# cell.net
KiCad netlist of a schematic drawn in EAGLE
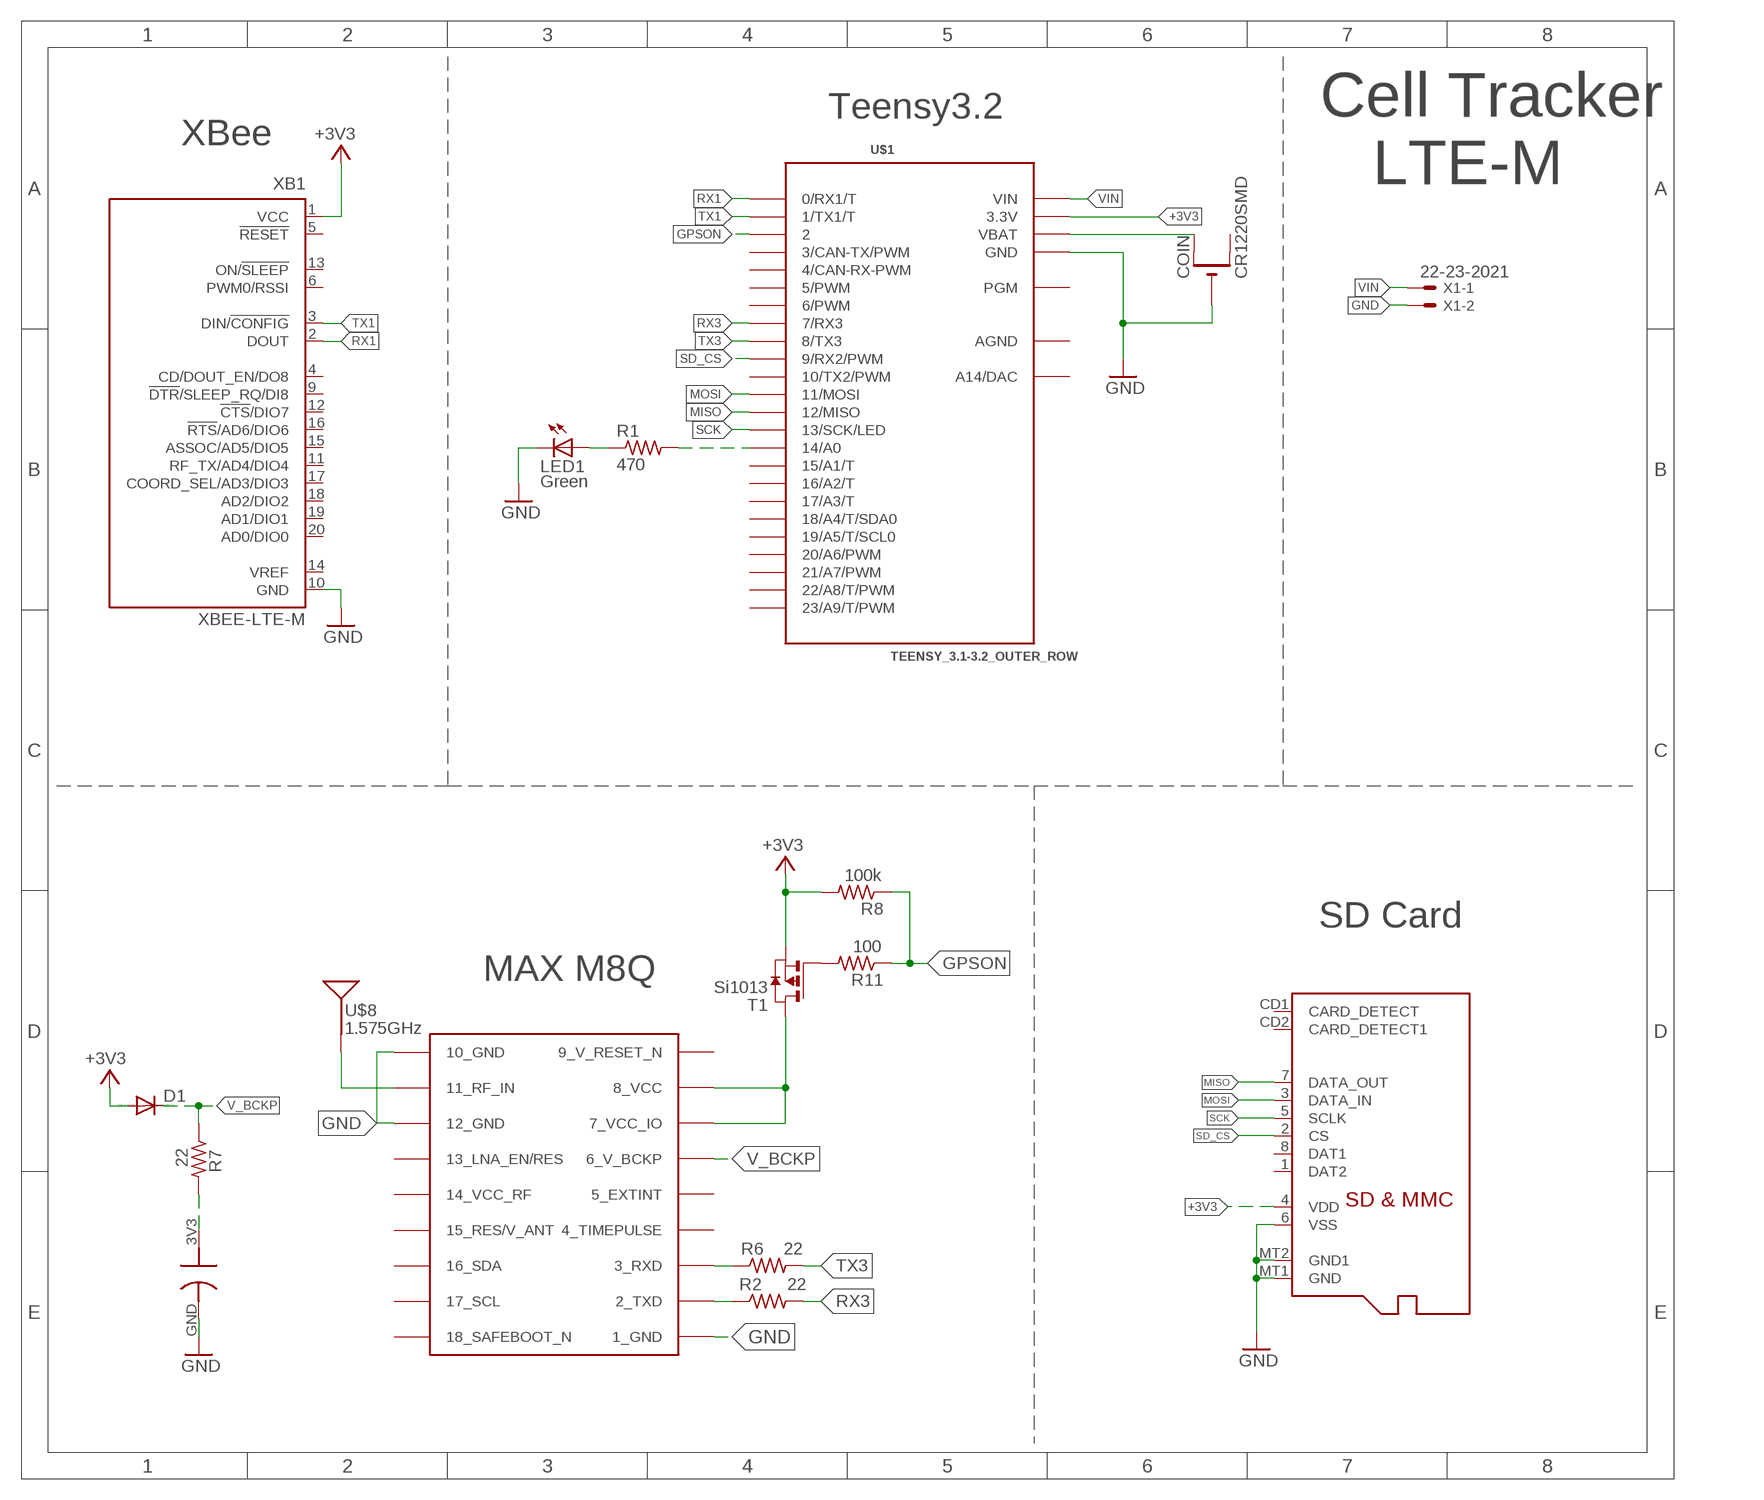
[diagram p0: schematic, sheet 1]

(export (version "E")
  (design (tool "Eeschema 10.0.6"))
  (components
    (comp (ref "C1")
      (value "DCK-3R3E204T614-E")
      (footprint "eagle-import:ELNASUPERCAP")
      (libsource (lib "eagle-import") (part "DCK-3R3E204T614-E"))
    )
    (comp (ref "COIN")
      (value "CR1220SMD")
      (footprint "eagle-import:CR1220-SMD")
      (libsource (lib "eagle-import") (part "CR1220SMT"))
    )
    (comp (ref "D1")
      (value "DIODE-SOD523")
      (footprint "eagle-import:SOD523")
      (libsource (lib "eagle-import") (part "DIODE-SOD523"))
    )
    (comp (ref "LED1")
      (value "Green")
      (footprint "eagle-import:CHIP-LED0603")
      (libsource (lib "eagle-import") (part "LEDCHIP-LED0603"))
    )
    (comp (ref "R1")
      (value "470")
      (footprint "eagle-import:R0603")
      (libsource (lib "eagle-import") (part "resistor_348_R-US_R0603"))
    )
    (comp (ref "R2")
      (value "22")
      (footprint "eagle-import:R0603")
      (libsource (lib "eagle-import") (part "R-US_R0603"))
    )
    (comp (ref "R6")
      (value "22")
      (footprint "eagle-import:R0603")
      (libsource (lib "eagle-import") (part "R-US_R0603"))
    )
    (comp (ref "R7")
      (value "22")
      (footprint "eagle-import:R0603")
      (libsource (lib "eagle-import") (part "R-US_R0603"))
    )
    (comp (ref "R8")
      (value "100k")
      (footprint "eagle-import:R0603")
      (libsource (lib "eagle-import") (part "R-US_R0603"))
    )
    (comp (ref "R11")
      (value "100")
      (footprint "eagle-import:R0603")
      (libsource (lib "eagle-import") (part "R-US_R0603"))
    )
    (comp (ref "T1")
      (value "Si1013")
      (footprint "eagle-import:SOT-23")
      (libsource (lib "eagle-import") (part "PMOSSOT23"))
    )
    (comp (ref "U$1")
      (value "TEENSY_3.1-3.2_OUTER_ROW")
      (footprint "eagle-import:TEENSY_3.0-3.2&LC_OUTER_ROW")
      (libsource (lib "eagle-import") (part "TEENSY_3.1-3.2_OUTER_ROW"))
    )
    (comp (ref "U$2")
      (value "MICROSD")
      (footprint "eagle-import:MICROSD")
      (libsource (lib "eagle-import") (part "MICROSD"))
    )
    (comp (ref "U$7")
      (value "MAX-M8")
      (footprint "eagle-import:MAX-M8")
      (libsource (lib "eagle-import") (part "MAX-M8"))
    )
    (comp (ref "U$8")
      (value "1.575GHz")
      (footprint "eagle-import:SPARKFUN-GPS_ANT-GPS-2X7MM")
      (libsource (lib "eagle-import") (part "SPARKFUN-GPS_ANTENNAGPS-2X7MM"))
    )
    (comp (ref "X1")
      (value "22-23-2021")
      (footprint "eagle-import:22-23-2021")
      (fields (field (name "MF") "MOLEX"))
      (libsource (lib "eagle-import") (part "22-23-2021"))
    )
    (comp (ref "XB1")
      (value "XBEE-LTE-M")
      (footprint "eagle-import:XBEE-PRO")
      (fields (field (name "MPN") "XBP24-AWI-001"))
      (libsource (lib "eagle-import") (part "XBEE-PRO"))
    )
  )
  (nets
    (net (code "1") (name "+3V3") (class "Default")
      (node (ref "D1") (pin "A") (pinfunction "A_A") (pintype "passive"))
      (node (ref "R8") (pin "2") (pinfunction "2_2") (pintype "passive"))
      (node (ref "T1") (pin "2") (pinfunction "S_2") (pintype "passive"))
      (node (ref "U$1") (pin "3.3V") (pinfunction "3.3V_3.3V") (pintype "power_in"))
      (node (ref "U$1") (pin "3.3V1") (pinfunction "3.3V_3.3V1") (pintype "power_in"))
      (node (ref "U$2") (pin "4") (pinfunction "VDD_4") (pintype "power_in"))
      (node (ref "XB1") (pin "1") (pinfunction "VCC_1") (pintype "power_in"))
    )
    (net (code "2") (name "/9_V_RESET_N") (class "Default")
      (node (ref "U$7") (pin "9_RESET_N") (pinfunction "9_V_RESET_N_9_RESET_N") (pintype "power_in"))
    )
    (net (code "3") (name "/AGND") (class "Default")
      (node (ref "U$1") (pin "AGND") (pinfunction "AGND_AGND") (pintype "power_in"))
    )
    (net (code "4") (name "GND") (class "Default")
      (node (ref "C1") (pin "GND") (pinfunction "GND_GND") (pintype "bidirectional"))
      (node (ref "COIN") (pin "-") (pinfunction "-_-") (pintype "passive"))
      (node (ref "LED1") (pin "C") (pinfunction "C_C") (pintype "passive"))
      (node (ref "U$1") (pin "GND") (pinfunction "GND_GND") (pintype "power_in"))
      (node (ref "U$1") (pin "GND1") (pinfunction "GND_GND1") (pintype "power_in"))
      (node (ref "U$2") (pin "6") (pinfunction "VSS_6") (pintype "power_in"))
      (node (ref "U$2") (pin "MT1") (pinfunction "GND_MT1") (pintype "power_in"))
      (node (ref "U$2") (pin "MT2") (pinfunction "GND1_MT2") (pintype "power_in"))
      (node (ref "U$7") (pin "10_GND") (pinfunction "10_GND_10_GND") (pintype "power_in"))
      (node (ref "U$7") (pin "12_GND") (pinfunction "12_GND_12_GND") (pintype "power_in"))
      (node (ref "U$7") (pin "1_GND") (pinfunction "1_GND_1_GND") (pintype "power_in"))
      (node (ref "X1") (pin "2") (pinfunction "S_2") (pintype "passive"))
      (node (ref "XB1") (pin "10") (pinfunction "GND_10") (pintype "power_in"))
    )
    (net (code "5") (name "GPSON") (class "Default")
      (node (ref "R11") (pin "1") (pinfunction "1_1") (pintype "passive"))
      (node (ref "R8") (pin "1") (pinfunction "1_1") (pintype "passive"))
      (node (ref "U$1") (pin "2") (pinfunction "2_2") (pintype "bidirectional"))
    )
    (net (code "6") (name "MISO") (class "Default")
      (node (ref "U$1") (pin "12") (pinfunction "12/MISO_12") (pintype "bidirectional"))
      (node (ref "U$2") (pin "7") (pinfunction "DATA_OUT_7") (pintype "output"))
    )
    (net (code "7") (name "MOSI") (class "Default")
      (node (ref "U$1") (pin "11") (pinfunction "11/MOSI_11") (pintype "bidirectional"))
      (node (ref "U$2") (pin "3") (pinfunction "DATA_IN_3") (pintype "input"))
    )
    (net (code "8") (name "Net-(C1-Pad3V3)") (class "Default")
      (node (ref "C1") (pin "3V3") (pinfunction "3V3_3V3") (pintype "bidirectional"))
      (node (ref "R7") (pin "2") (pinfunction "2_2") (pintype "passive"))
    )
    (net (code "9") (name "Net-(COIN-+)") (class "Default")
      (node (ref "COIN") (pin "+$1") (pinfunction "+_+$1") (pintype "passive"))
      (node (ref "U$1") (pin "VBAT") (pinfunction "VBAT_VBAT") (pintype "power_in"))
    )
    (net (code "10") (name "Net-(LED1-PadA)") (class "Default")
      (node (ref "LED1") (pin "A") (pinfunction "A_A") (pintype "passive"))
      (node (ref "R1") (pin "1") (pinfunction "1_1") (pintype "passive"))
    )
    (net (code "11") (name "Net-(R1-Pad2)") (class "Default")
      (node (ref "R1") (pin "2") (pinfunction "2_2") (pintype "passive"))
      (node (ref "U$1") (pin "14/A0") (pinfunction "14/A0_14/A0") (pintype "bidirectional"))
    )
    (net (code "12") (name "Net-(R2-Pad1)") (class "Default")
      (node (ref "R2") (pin "1") (pinfunction "1_1") (pintype "passive"))
      (node (ref "U$7") (pin "2_TXD") (pinfunction "2_TXD_2_TXD") (pintype "bidirectional"))
    )
    (net (code "13") (name "Net-(R6-Pad1)") (class "Default")
      (node (ref "R6") (pin "1") (pinfunction "1_1") (pintype "passive"))
      (node (ref "U$7") (pin "3_RXD") (pinfunction "3_RXD_3_RXD") (pintype "bidirectional"))
    )
    (net (code "14") (name "Net-(T1-D)") (class "Default")
      (node (ref "T1") (pin "1") (pinfunction "D_1") (pintype "passive"))
      (node (ref "U$7") (pin "7_VCC_IO") (pinfunction "7_VCC_IO_7_VCC_IO") (pintype "power_in"))
      (node (ref "U$7") (pin "8_VCC") (pinfunction "8_VCC_8_VCC") (pintype "power_in"))
    )
    (net (code "15") (name "Net-(T1-G)") (class "Default")
      (node (ref "R11") (pin "2") (pinfunction "2_2") (pintype "passive"))
      (node (ref "T1") (pin "3") (pinfunction "G_3") (pintype "passive"))
    )
    (net (code "16") (name "Net-(U$8-SIGNAL)") (class "Default")
      (node (ref "U$7") (pin "11_RF_IN") (pinfunction "11_RF_IN_11_RF_IN") (pintype "bidirectional"))
      (node (ref "U$8") (pin "1") (pinfunction "SIGNAL_1") (pintype "bidirectional"))
    )
    (net (code "17") (name "RX1") (class "Default")
      (node (ref "U$1") (pin "0") (pinfunction "0/RX1/T_0") (pintype "bidirectional"))
      (node (ref "XB1") (pin "2") (pinfunction "DOUT_2") (pintype "output"))
    )
    (net (code "18") (name "RX3") (class "Default")
      (node (ref "R2") (pin "2") (pinfunction "2_2") (pintype "passive"))
      (node (ref "U$1") (pin "7") (pinfunction "7/RX3_7") (pintype "bidirectional"))
    )
    (net (code "19") (name "SCK") (class "Default")
      (node (ref "U$1") (pin "13") (pinfunction "13/SCK/LED_13") (pintype "bidirectional"))
      (node (ref "U$2") (pin "5") (pinfunction "SCLK_5") (pintype "input"))
    )
    (net (code "20") (name "SD_CS") (class "Default")
      (node (ref "U$1") (pin "9") (pinfunction "9/RX2/PWM_9") (pintype "bidirectional"))
      (node (ref "U$2") (pin "2") (pinfunction "CS_2") (pintype "input"))
    )
    (net (code "21") (name "TX1") (class "Default")
      (node (ref "U$1") (pin "1") (pinfunction "1/TX1/T_1") (pintype "bidirectional"))
      (node (ref "XB1") (pin "3") (pinfunction "DIN/~{CONFIG}_3") (pintype "input"))
    )
    (net (code "22") (name "TX3") (class "Default")
      (node (ref "R6") (pin "2") (pinfunction "2_2") (pintype "passive"))
      (node (ref "U$1") (pin "8") (pinfunction "8/TX3_8") (pintype "bidirectional"))
    )
    (net (code "23") (name "VIN") (class "Default")
      (node (ref "U$1") (pin "VIN") (pinfunction "VIN_VIN") (pintype "power_in"))
      (node (ref "X1") (pin "1") (pinfunction "S_1") (pintype "passive"))
    )
    (net (code "24") (name "V_BCKP") (class "Default")
      (node (ref "D1") (pin "C") (pinfunction "C_C") (pintype "passive"))
      (node (ref "R7") (pin "1") (pinfunction "1_1") (pintype "passive"))
      (node (ref "U$7") (pin "6_V_BCKP") (pinfunction "6_V_BCKP_6_V_BCKP") (pintype "bidirectional"))
    )
    (net (code "25") (name "unconnected-(COIN-+1-Pad+$2)") (class "Default")
      (node (ref "COIN") (pin "+$2") (pinfunction "+1_+$2") (pintype "passive"))
    )
    (net (code "26") (name "unconnected-(U$1-3{slash}CAN-TX{slash}PWM-Pad3)") (class "Default")
      (node (ref "U$1") (pin "3") (pinfunction "3/CAN-TX/PWM_3") (pintype "bidirectional"))
    )
    (net (code "27") (name "unconnected-(U$1-4{slash}CAN-RX-PWM-Pad4)") (class "Default")
      (node (ref "U$1") (pin "4") (pinfunction "4/CAN-RX-PWM_4") (pintype "bidirectional"))
    )
    (net (code "28") (name "unconnected-(U$1-5{slash}PWM-Pad5)") (class "Default")
      (node (ref "U$1") (pin "5") (pinfunction "5/PWM_5") (pintype "bidirectional"))
    )
    (net (code "29") (name "unconnected-(U$1-6{slash}PWM-Pad6)") (class "Default")
      (node (ref "U$1") (pin "6") (pinfunction "6/PWM_6") (pintype "bidirectional"))
    )
    (net (code "30") (name "unconnected-(U$1-10{slash}TX2{slash}PWM-Pad10)") (class "Default")
      (node (ref "U$1") (pin "10") (pinfunction "10/TX2/PWM_10") (pintype "bidirectional"))
    )
    (net (code "31") (name "unconnected-(U$1-15{slash}A1{slash}T-Pad15{slash}A1)") (class "Default")
      (node (ref "U$1") (pin "15/A1") (pinfunction "15/A1/T_15/A1") (pintype "bidirectional"))
    )
    (net (code "32") (name "unconnected-(U$1-16{slash}A2{slash}T-Pad16{slash}A2)") (class "Default")
      (node (ref "U$1") (pin "16/A2") (pinfunction "16/A2/T_16/A2") (pintype "bidirectional"))
    )
    (net (code "33") (name "unconnected-(U$1-17{slash}A3{slash}T-Pad17{slash}A3)") (class "Default")
      (node (ref "U$1") (pin "17/A3") (pinfunction "17/A3/T_17/A3") (pintype "bidirectional"))
    )
    (net (code "34") (name "unconnected-(U$1-18{slash}A4{slash}T{slash}SDA0-Pad18{slash}A4)") (class "Default")
      (node (ref "U$1") (pin "18/A4") (pinfunction "18/A4/T/SDA0_18/A4") (pintype "bidirectional"))
    )
    (net (code "35") (name "unconnected-(U$1-19{slash}A5{slash}T{slash}SCL0-Pad19{slash}A5)") (class "Default")
      (node (ref "U$1") (pin "19/A5") (pinfunction "19/A5/T/SCL0_19/A5") (pintype "bidirectional"))
    )
    (net (code "36") (name "unconnected-(U$1-20{slash}A6{slash}PWM-Pad20{slash}A6)") (class "Default")
      (node (ref "U$1") (pin "20/A6") (pinfunction "20/A6/PWM_20/A6") (pintype "bidirectional"))
    )
    (net (code "37") (name "unconnected-(U$1-21{slash}A7{slash}PWM-Pad21{slash}A7)") (class "Default")
      (node (ref "U$1") (pin "21/A7") (pinfunction "21/A7/PWM_21/A7") (pintype "bidirectional"))
    )
    (net (code "38") (name "unconnected-(U$1-22{slash}A8{slash}T{slash}PWM-Pad22{slash}A8)") (class "Default")
      (node (ref "U$1") (pin "22/A8") (pinfunction "22/A8/T/PWM_22/A8") (pintype "bidirectional"))
    )
    (net (code "39") (name "unconnected-(U$1-23{slash}A9{slash}T{slash}PWM-Pad23{slash}A9)") (class "Default")
      (node (ref "U$1") (pin "23/A9") (pinfunction "23/A9/T/PWM_23/A9") (pintype "bidirectional"))
    )
    (net (code "40") (name "unconnected-(U$1-A14{slash}DAC-PadRESET{slash}DAC)") (class "Default")
      (node (ref "U$1") (pin "RESET/DAC") (pinfunction "A14/DAC_RESET/DAC") (pintype "bidirectional"))
    )
    (net (code "41") (name "unconnected-(U$1-PadPGM)") (class "Default")
      (node (ref "U$1") (pin "PGM") (pinfunction "PGM_PGM") (pintype "bidirectional"))
    )
    (net (code "42") (name "unconnected-(U$2-CARD_DETECT-PadCD1)") (class "Default")
      (node (ref "U$2") (pin "CD1") (pinfunction "CARD_DETECT_CD1") (pintype "passive"))
    )
    (net (code "43") (name "unconnected-(U$2-CARD_DETECT1-PadCD2)") (class "Default")
      (node (ref "U$2") (pin "CD2") (pinfunction "CARD_DETECT1_CD2") (pintype "passive"))
    )
    (net (code "44") (name "unconnected-(U$2-DAT1-Pad8)") (class "Default")
      (node (ref "U$2") (pin "8") (pinfunction "DAT1_8") (pintype "bidirectional"))
    )
    (net (code "45") (name "unconnected-(U$2-DAT2-Pad1)") (class "Default")
      (node (ref "U$2") (pin "1") (pinfunction "DAT2_1") (pintype "bidirectional"))
    )
    (net (code "46") (name "unconnected-(U$7-13_LNA_EN{slash}RES-Pad13_LNA_EN)") (class "Default")
      (node (ref "U$7") (pin "13_LNA_EN") (pinfunction "13_LNA_EN/RES_13_LNA_EN") (pintype "bidirectional"))
    )
    (net (code "47") (name "unconnected-(U$7-15_RES{slash}V_ANT-Pad15_V_ANT{slash}RESERVED)") (class "Default")
      (node (ref "U$7") (pin "15_V_ANT/RESERVED") (pinfunction "15_RES/V_ANT_15_V_ANT/RESERVED") (pintype "bidirectional"))
    )
    (net (code "48") (name "unconnected-(U$7-Pad4_TIMEPULSE)") (class "Default")
      (node (ref "U$7") (pin "4_TIMEPULSE") (pinfunction "4_TIMEPULSE_4_TIMEPULSE") (pintype "bidirectional"))
    )
    (net (code "49") (name "unconnected-(U$7-Pad5_EXTINT)") (class "Default")
      (node (ref "U$7") (pin "5_EXTINT") (pinfunction "5_EXTINT_5_EXTINT") (pintype "bidirectional"))
    )
    (net (code "50") (name "unconnected-(U$7-Pad14_VCC_RF)") (class "Default")
      (node (ref "U$7") (pin "14_VCC_RF") (pinfunction "14_VCC_RF_14_VCC_RF") (pintype "bidirectional"))
    )
    (net (code "51") (name "unconnected-(U$7-Pad16_SDA)") (class "Default")
      (node (ref "U$7") (pin "16_SDA") (pinfunction "16_SDA_16_SDA") (pintype "bidirectional"))
    )
    (net (code "52") (name "unconnected-(U$7-Pad17_SCL)") (class "Default")
      (node (ref "U$7") (pin "17_SCL") (pinfunction "17_SCL_17_SCL") (pintype "bidirectional"))
    )
    (net (code "53") (name "unconnected-(U$7-Pad18_SAFEBOOT_N)") (class "Default")
      (node (ref "U$7") (pin "18_SAFEBOOT_N") (pinfunction "18_SAFEBOOT_N_18_SAFEBOOT_N") (pintype "bidirectional"))
    )
    (net (code "54") (name "unconnected-(XB1-AD0{slash}DIO0-Pad20)") (class "Default")
      (node (ref "XB1") (pin "20") (pinfunction "AD0/DIO0_20") (pintype "bidirectional"))
    )
    (net (code "55") (name "unconnected-(XB1-AD1{slash}DIO1-Pad19)") (class "Default")
      (node (ref "XB1") (pin "19") (pinfunction "AD1/DIO1_19") (pintype "bidirectional"))
    )
    (net (code "56") (name "unconnected-(XB1-AD2{slash}DIO2-Pad18)") (class "Default")
      (node (ref "XB1") (pin "18") (pinfunction "AD2/DIO2_18") (pintype "bidirectional"))
    )
    (net (code "57") (name "unconnected-(XB1-ASSOC{slash}AD5{slash}DIO5-Pad15)") (class "Default")
      (node (ref "XB1") (pin "15") (pinfunction "ASSOC/AD5/DIO5_15") (pintype "bidirectional"))
    )
    (net (code "58") (name "unconnected-(XB1-CD{slash}DOUT_EN{slash}DO8-Pad4)") (class "Default")
      (node (ref "XB1") (pin "4") (pinfunction "CD/DOUT_EN/DO8_4") (pintype "output"))
    )
    (net (code "59") (name "unconnected-(XB1-COORD_SEL{slash}AD3{slash}DIO3-Pad17)") (class "Default")
      (node (ref "XB1") (pin "17") (pinfunction "COORD_SEL/AD3/DIO3_17") (pintype "bidirectional"))
    )
    (net (code "60") (name "unconnected-(XB1-ON{slash}~{SLEEP}-Pad13)") (class "Default")
      (node (ref "XB1") (pin "13") (pinfunction "ON/~{SLEEP}_13") (pintype "output"))
    )
    (net (code "61") (name "unconnected-(XB1-PWM0{slash}RSSI-Pad6)") (class "Default")
      (node (ref "XB1") (pin "6") (pinfunction "PWM0/RSSI_6") (pintype "output"))
    )
    (net (code "62") (name "unconnected-(XB1-RF_TX{slash}AD4{slash}DIO4-Pad11)") (class "Default")
      (node (ref "XB1") (pin "11") (pinfunction "RF_TX/AD4/DIO4_11") (pintype "bidirectional"))
    )
    (net (code "63") (name "unconnected-(XB1-VREF-Pad14)") (class "Default")
      (node (ref "XB1") (pin "14") (pinfunction "VREF_14") (pintype "input"))
    )
    (net (code "64") (name "unconnected-(XB1-~{CTS}{slash}DIO7-Pad12)") (class "Default")
      (node (ref "XB1") (pin "12") (pinfunction "~{CTS}/DIO7_12") (pintype "bidirectional"))
    )
    (net (code "65") (name "unconnected-(XB1-~{DTR}{slash}SLEEP_RQ{slash}DI8-Pad9)") (class "Default")
      (node (ref "XB1") (pin "9") (pinfunction "~{DTR}/SLEEP_RQ/DI8_9") (pintype "bidirectional"))
    )
    (net (code "66") (name "unconnected-(XB1-~{RESET}-Pad5)") (class "Default")
      (node (ref "XB1") (pin "5") (pinfunction "~{RESET}_5") (pintype "input"))
    )
    (net (code "67") (name "unconnected-(XB1-~{RTS}{slash}AD6{slash}DIO6-Pad16)") (class "Default")
      (node (ref "XB1") (pin "16") (pinfunction "~{RTS}/AD6/DIO6_16") (pintype "bidirectional"))
    )
  )
)
